# MicrobitBoardExtend.net
KiCad netlist of a schematic drawn in Altium Designer
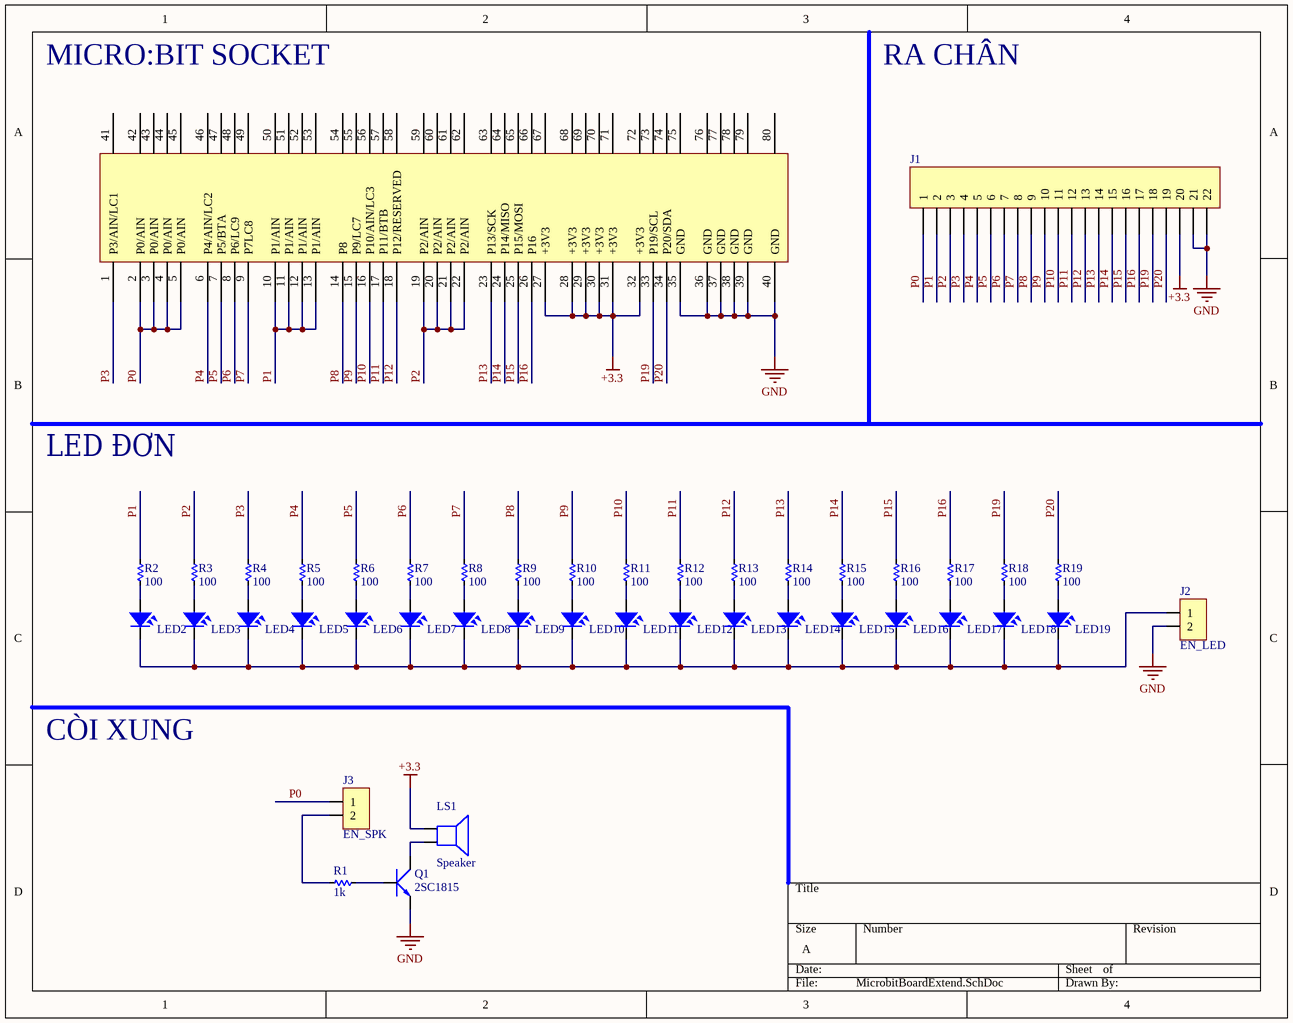
[diagram p0: MicrobitBoardExtend.SchDoc]

(export (version "E")
  (design (tool "Eeschema 10.0.6"))
  (components
    (comp (ref "BBC1")
      (value "BBC_SOCKET")
      (footprint "BBC_SK_DIP")
      (libsource (lib "microbit") (part "BBC_SOCKET"))
    )
    (comp (ref "J1")
      (value "JP22")
      (footprint "JP22-D1T")
      (description "WR-PHD 2.54 mm Angled Socket Header")
      (fields
        (field (name "MANUFACTURER") "Würth Elektronik eiSos GmbH")
        (field (name "PARTNO") "613022143121")
        (field (name "CREATED BY") "Karrer Zheng")
      )
      (libsource (lib "LIBRARY") (part "JP22"))
    )
    (comp (ref "J2")
      (value "EN_LED")
      (footprint "JP2-CLOSED")
      (description "WR-PHD 2.54 mm Angled Socket Header")
      (fields
        (field (name "MANUFACTURER") "Würth Elektronik eiSos GmbH")
        (field (name "PARTNO") "613002143121")
        (field (name "CREATED BY") "Karrer Zheng")
      )
      (libsource (lib "LIBRARY") (part "JP2"))
    )
    (comp (ref "J3")
      (value "EN_SPK")
      (footprint "JP2-CLOSED")
      (description "WR-PHD 2.54 mm Angled Socket Header")
      (fields
        (field (name "MANUFACTURER") "Würth Elektronik eiSos GmbH")
        (field (name "PARTNO") "613002143121")
        (field (name "CREATED BY") "Karrer Zheng")
      )
      (libsource (lib "LIBRARY") (part "JP2"))
    )
    (comp (ref "LED2")
      (value "LED")
      (footprint "LED-3MM-BLUE")
      (description "LED Single colour Green and Red")
      (libsource (lib "LIBRARY") (part "LED"))
    )
    (comp (ref "LED3")
      (value "LED")
      (footprint "LED-3MM-BLUE")
      (description "LED Single colour Green and Red")
      (libsource (lib "LIBRARY") (part "LED"))
    )
    (comp (ref "LED4")
      (value "LED")
      (footprint "LED-3MM-BLUE")
      (description "LED Single colour Green and Red")
      (libsource (lib "LIBRARY") (part "LED"))
    )
    (comp (ref "LED5")
      (value "LED")
      (footprint "LED-3MM-BLUE")
      (description "LED Single colour Green and Red")
      (libsource (lib "LIBRARY") (part "LED"))
    )
    (comp (ref "LED6")
      (value "LED")
      (footprint "LED-3MM-BLUE")
      (description "LED Single colour Green and Red")
      (libsource (lib "LIBRARY") (part "LED"))
    )
    (comp (ref "LED7")
      (value "LED")
      (footprint "LED-3MM-BLUE")
      (description "LED Single colour Green and Red")
      (libsource (lib "LIBRARY") (part "LED"))
    )
    (comp (ref "LED8")
      (value "LED")
      (footprint "LED-3MM-BLUE")
      (description "LED Single colour Green and Red")
      (libsource (lib "LIBRARY") (part "LED"))
    )
    (comp (ref "LED9")
      (value "LED")
      (footprint "LED-3MM-BLUE")
      (description "LED Single colour Green and Red")
      (libsource (lib "LIBRARY") (part "LED"))
    )
    (comp (ref "LED10")
      (value "LED")
      (footprint "LED-3MM-BLUE")
      (description "LED Single colour Green and Red")
      (libsource (lib "LIBRARY") (part "LED"))
    )
    (comp (ref "LED11")
      (value "LED")
      (footprint "LED-3MM-BLUE")
      (description "LED Single colour Green and Red")
      (libsource (lib "LIBRARY") (part "LED"))
    )
    (comp (ref "LED12")
      (value "LED")
      (footprint "LED-3MM-BLUE")
      (description "LED Single colour Green and Red")
      (libsource (lib "LIBRARY") (part "LED"))
    )
    (comp (ref "LED13")
      (value "LED")
      (footprint "LED-3MM-BLUE")
      (description "LED Single colour Green and Red")
      (libsource (lib "LIBRARY") (part "LED"))
    )
    (comp (ref "LED14")
      (value "LED")
      (footprint "LED-3MM-BLUE")
      (description "LED Single colour Green and Red")
      (libsource (lib "LIBRARY") (part "LED"))
    )
    (comp (ref "LED15")
      (value "LED")
      (footprint "LED-3MM-BLUE")
      (description "LED Single colour Green and Red")
      (libsource (lib "LIBRARY") (part "LED"))
    )
    (comp (ref "LED16")
      (value "LED")
      (footprint "LED-3MM-BLUE")
      (description "LED Single colour Green and Red")
      (libsource (lib "LIBRARY") (part "LED"))
    )
    (comp (ref "LED17")
      (value "LED")
      (footprint "LED-3MM-BLUE")
      (description "LED Single colour Green and Red")
      (libsource (lib "LIBRARY") (part "LED"))
    )
    (comp (ref "LED18")
      (value "LED")
      (footprint "LED-3MM-BLUE")
      (description "LED Single colour Green and Red")
      (libsource (lib "LIBRARY") (part "LED"))
    )
    (comp (ref "LED19")
      (value "LED")
      (footprint "LED-3MM-BLUE")
      (description "LED Single colour Green and Red")
      (libsource (lib "LIBRARY") (part "LED"))
    )
    (comp (ref "LS1")
      (value "Speaker")
      (footprint "SPEAKER")
      (description "Loudspeaker")
      (fields (field (name "PUBLISHER") "Altium Limited"))
      (libsource (lib "LIBRARY") (part "Speaker"))
    )
    (comp (ref "Q1")
      (value "2SC1815")
      (footprint "SOT23-321")
      (description "NPN 600mW, ECB")
      (libsource (lib "LIBRARY") (part "2SC1815"))
    )
    (comp (ref "R1")
      (value "1k")
      (footprint "RES-SMD-0805")
      (description "Resistor")
      (fields
        (field (name "MANUFACTURER") "Generic Components")
        (field (name "PUBLISHER") "Altium Hobart Technology Centre")
      )
      (libsource (lib "LIBRARY") (part "Res-SMD"))
    )
    (comp (ref "R2")
      (value "100")
      (footprint "RES-SMD-0805")
      (description "Resistor")
      (fields
        (field (name "MANUFACTURER") "Generic Components")
        (field (name "PUBLISHER") "Altium Hobart Technology Centre")
      )
      (libsource (lib "LIBRARY") (part "Res-SMD"))
    )
    (comp (ref "R3")
      (value "100")
      (footprint "RES-SMD-0805")
      (description "Resistor")
      (fields
        (field (name "MANUFACTURER") "Generic Components")
        (field (name "PUBLISHER") "Altium Hobart Technology Centre")
      )
      (libsource (lib "LIBRARY") (part "Res-SMD"))
    )
    (comp (ref "R4")
      (value "100")
      (footprint "RES-SMD-0805")
      (description "Resistor")
      (fields
        (field (name "MANUFACTURER") "Generic Components")
        (field (name "PUBLISHER") "Altium Hobart Technology Centre")
      )
      (libsource (lib "LIBRARY") (part "Res-SMD"))
    )
    (comp (ref "R5")
      (value "100")
      (footprint "RES-SMD-0805")
      (description "Resistor")
      (fields
        (field (name "MANUFACTURER") "Generic Components")
        (field (name "PUBLISHER") "Altium Hobart Technology Centre")
      )
      (libsource (lib "LIBRARY") (part "Res-SMD"))
    )
    (comp (ref "R6")
      (value "100")
      (footprint "RES-SMD-0805")
      (description "Resistor")
      (fields
        (field (name "MANUFACTURER") "Generic Components")
        (field (name "PUBLISHER") "Altium Hobart Technology Centre")
      )
      (libsource (lib "LIBRARY") (part "Res-SMD"))
    )
    (comp (ref "R7")
      (value "100")
      (footprint "RES-SMD-0805")
      (description "Resistor")
      (fields
        (field (name "MANUFACTURER") "Generic Components")
        (field (name "PUBLISHER") "Altium Hobart Technology Centre")
      )
      (libsource (lib "LIBRARY") (part "Res-SMD"))
    )
    (comp (ref "R8")
      (value "100")
      (footprint "RES-SMD-0805")
      (description "Resistor")
      (fields
        (field (name "MANUFACTURER") "Generic Components")
        (field (name "PUBLISHER") "Altium Hobart Technology Centre")
      )
      (libsource (lib "LIBRARY") (part "Res-SMD"))
    )
    (comp (ref "R9")
      (value "100")
      (footprint "RES-SMD-0805")
      (description "Resistor")
      (fields
        (field (name "MANUFACTURER") "Generic Components")
        (field (name "PUBLISHER") "Altium Hobart Technology Centre")
      )
      (libsource (lib "LIBRARY") (part "Res-SMD"))
    )
    (comp (ref "R10")
      (value "100")
      (footprint "RES-SMD-0805")
      (description "Resistor")
      (fields
        (field (name "MANUFACTURER") "Generic Components")
        (field (name "PUBLISHER") "Altium Hobart Technology Centre")
      )
      (libsource (lib "LIBRARY") (part "Res-SMD"))
    )
    (comp (ref "R11")
      (value "100")
      (footprint "RES-SMD-0805")
      (description "Resistor")
      (fields
        (field (name "MANUFACTURER") "Generic Components")
        (field (name "PUBLISHER") "Altium Hobart Technology Centre")
      )
      (libsource (lib "LIBRARY") (part "Res-SMD"))
    )
    (comp (ref "R12")
      (value "100")
      (footprint "RES-SMD-0805")
      (description "Resistor")
      (fields
        (field (name "MANUFACTURER") "Generic Components")
        (field (name "PUBLISHER") "Altium Hobart Technology Centre")
      )
      (libsource (lib "LIBRARY") (part "Res-SMD"))
    )
    (comp (ref "R13")
      (value "100")
      (footprint "RES-SMD-0805")
      (description "Resistor")
      (fields
        (field (name "MANUFACTURER") "Generic Components")
        (field (name "PUBLISHER") "Altium Hobart Technology Centre")
      )
      (libsource (lib "LIBRARY") (part "Res-SMD"))
    )
    (comp (ref "R14")
      (value "100")
      (footprint "RES-SMD-0805")
      (description "Resistor")
      (fields
        (field (name "MANUFACTURER") "Generic Components")
        (field (name "PUBLISHER") "Altium Hobart Technology Centre")
      )
      (libsource (lib "LIBRARY") (part "Res-SMD"))
    )
    (comp (ref "R15")
      (value "100")
      (footprint "RES-SMD-0805")
      (description "Resistor")
      (fields
        (field (name "MANUFACTURER") "Generic Components")
        (field (name "PUBLISHER") "Altium Hobart Technology Centre")
      )
      (libsource (lib "LIBRARY") (part "Res-SMD"))
    )
    (comp (ref "R16")
      (value "100")
      (footprint "RES-SMD-0805")
      (description "Resistor")
      (fields
        (field (name "MANUFACTURER") "Generic Components")
        (field (name "PUBLISHER") "Altium Hobart Technology Centre")
      )
      (libsource (lib "LIBRARY") (part "Res-SMD"))
    )
    (comp (ref "R17")
      (value "100")
      (footprint "RES-SMD-0805")
      (description "Resistor")
      (fields
        (field (name "MANUFACTURER") "Generic Components")
        (field (name "PUBLISHER") "Altium Hobart Technology Centre")
      )
      (libsource (lib "LIBRARY") (part "Res-SMD"))
    )
    (comp (ref "R18")
      (value "100")
      (footprint "RES-SMD-0805")
      (description "Resistor")
      (fields
        (field (name "MANUFACTURER") "Generic Components")
        (field (name "PUBLISHER") "Altium Hobart Technology Centre")
      )
      (libsource (lib "LIBRARY") (part "Res-SMD"))
    )
    (comp (ref "R19")
      (value "100")
      (footprint "RES-SMD-0805")
      (description "Resistor")
      (fields
        (field (name "MANUFACTURER") "Generic Components")
        (field (name "PUBLISHER") "Altium Hobart Technology Centre")
      )
      (libsource (lib "LIBRARY") (part "Res-SMD"))
    )
  )
  (nets
    (net (code "1") (name "+3.3") (class "Default")
      (node (ref "BBC1") (pin "27") (pinfunction "+3V3_27") (pintype "passive"))
      (node (ref "BBC1") (pin "28") (pinfunction "+3V3_28") (pintype "passive"))
      (node (ref "BBC1") (pin "29") (pinfunction "+3V3_29") (pintype "passive"))
      (node (ref "BBC1") (pin "30") (pinfunction "+3V3_30") (pintype "passive"))
      (node (ref "BBC1") (pin "31") (pinfunction "+3V3_31") (pintype "passive"))
      (node (ref "BBC1") (pin "32") (pinfunction "+3V3_32") (pintype "passive"))
      (node (ref "J1") (pin "20") (pinfunction "20_20") (pintype "passive"))
      (node (ref "LS1") (pin "1") (pinfunction "1_1") (pintype "passive"))
    )
    (net (code "2") (name "/P0") (class "Default")
      (node (ref "BBC1") (pin "2") (pinfunction "P0/AIN_2") (pintype "passive"))
      (node (ref "BBC1") (pin "3") (pinfunction "P0/AIN_3") (pintype "passive"))
      (node (ref "BBC1") (pin "4") (pinfunction "P0/AIN_4") (pintype "passive"))
      (node (ref "BBC1") (pin "5") (pinfunction "P0/AIN_5") (pintype "passive"))
      (node (ref "J1") (pin "1") (pinfunction "1_1") (pintype "passive"))
      (node (ref "J3") (pin "1") (pinfunction "1_1") (pintype "passive"))
    )
    (net (code "3") (name "/P1") (class "Default")
      (node (ref "BBC1") (pin "10") (pinfunction "P1/AIN_10") (pintype "passive"))
      (node (ref "BBC1") (pin "11") (pinfunction "P1/AIN_11") (pintype "passive"))
      (node (ref "BBC1") (pin "12") (pinfunction "P1/AIN_12") (pintype "passive"))
      (node (ref "BBC1") (pin "13") (pinfunction "P1/AIN_13") (pintype "passive"))
      (node (ref "J1") (pin "2") (pinfunction "2_2") (pintype "passive"))
      (node (ref "R2") (pin "2") (pinfunction "2_2") (pintype "passive"))
    )
    (net (code "4") (name "/P2") (class "Default")
      (node (ref "BBC1") (pin "19") (pinfunction "P2/AIN_19") (pintype "passive"))
      (node (ref "BBC1") (pin "20") (pinfunction "P2/AIN_20") (pintype "passive"))
      (node (ref "BBC1") (pin "21") (pinfunction "P2/AIN_21") (pintype "passive"))
      (node (ref "BBC1") (pin "22") (pinfunction "P2/AIN_22") (pintype "passive"))
      (node (ref "J1") (pin "3") (pinfunction "3_3") (pintype "passive"))
      (node (ref "R3") (pin "2") (pinfunction "2_2") (pintype "passive"))
    )
    (net (code "5") (name "/P3") (class "Default")
      (node (ref "BBC1") (pin "1") (pinfunction "P3/AIN/LC1_1") (pintype "passive"))
      (node (ref "J1") (pin "4") (pinfunction "4_4") (pintype "passive"))
      (node (ref "R4") (pin "2") (pinfunction "2_2") (pintype "passive"))
    )
    (net (code "6") (name "/P4") (class "Default")
      (node (ref "BBC1") (pin "6") (pinfunction "P4/AIN/LC2_6") (pintype "passive"))
      (node (ref "J1") (pin "5") (pinfunction "5_5") (pintype "passive"))
      (node (ref "R5") (pin "2") (pinfunction "2_2") (pintype "passive"))
    )
    (net (code "7") (name "/P5") (class "Default")
      (node (ref "BBC1") (pin "7") (pinfunction "P5/BTA_7") (pintype "passive"))
      (node (ref "J1") (pin "6") (pinfunction "6_6") (pintype "passive"))
      (node (ref "R6") (pin "2") (pinfunction "2_2") (pintype "passive"))
    )
    (net (code "8") (name "/P6") (class "Default")
      (node (ref "BBC1") (pin "8") (pinfunction "P6/LC9_8") (pintype "passive"))
      (node (ref "J1") (pin "7") (pinfunction "7_7") (pintype "passive"))
      (node (ref "R7") (pin "2") (pinfunction "2_2") (pintype "passive"))
    )
    (net (code "9") (name "/P7") (class "Default")
      (node (ref "BBC1") (pin "9") (pinfunction "P7LC8_9") (pintype "passive"))
      (node (ref "J1") (pin "8") (pinfunction "8_8") (pintype "passive"))
      (node (ref "R8") (pin "2") (pinfunction "2_2") (pintype "passive"))
    )
    (net (code "10") (name "/P8") (class "Default")
      (node (ref "BBC1") (pin "14") (pinfunction "P8_14") (pintype "passive"))
      (node (ref "J1") (pin "9") (pinfunction "9_9") (pintype "passive"))
      (node (ref "R9") (pin "2") (pinfunction "2_2") (pintype "passive"))
    )
    (net (code "11") (name "/P9") (class "Default")
      (node (ref "BBC1") (pin "15") (pinfunction "P9/LC7_15") (pintype "passive"))
      (node (ref "J1") (pin "10") (pinfunction "10_10") (pintype "passive"))
      (node (ref "R10") (pin "2") (pinfunction "2_2") (pintype "passive"))
    )
    (net (code "12") (name "/P10") (class "Default")
      (node (ref "BBC1") (pin "16") (pinfunction "P10/AIN/LC3_16") (pintype "passive"))
      (node (ref "J1") (pin "11") (pinfunction "11_11") (pintype "passive"))
      (node (ref "R11") (pin "2") (pinfunction "2_2") (pintype "passive"))
    )
    (net (code "13") (name "/P11") (class "Default")
      (node (ref "BBC1") (pin "17") (pinfunction "P11/BTB_17") (pintype "passive"))
      (node (ref "J1") (pin "12") (pinfunction "12_12") (pintype "passive"))
      (node (ref "R12") (pin "2") (pinfunction "2_2") (pintype "passive"))
    )
    (net (code "14") (name "/P12") (class "Default")
      (node (ref "BBC1") (pin "18") (pinfunction "P12/RESERVED_18") (pintype "passive"))
      (node (ref "J1") (pin "13") (pinfunction "13_13") (pintype "passive"))
      (node (ref "R13") (pin "2") (pinfunction "2_2") (pintype "passive"))
    )
    (net (code "15") (name "/P13") (class "Default")
      (node (ref "BBC1") (pin "23") (pinfunction "P13/SCK_23") (pintype "passive"))
      (node (ref "J1") (pin "14") (pinfunction "14_14") (pintype "passive"))
      (node (ref "R14") (pin "2") (pinfunction "2_2") (pintype "passive"))
    )
    (net (code "16") (name "/P14") (class "Default")
      (node (ref "BBC1") (pin "24") (pinfunction "P14/MISO_24") (pintype "passive"))
      (node (ref "J1") (pin "15") (pinfunction "15_15") (pintype "passive"))
      (node (ref "R15") (pin "2") (pinfunction "2_2") (pintype "passive"))
    )
    (net (code "17") (name "/P15") (class "Default")
      (node (ref "BBC1") (pin "25") (pinfunction "P15/MOSI_25") (pintype "passive"))
      (node (ref "J1") (pin "16") (pinfunction "16_16") (pintype "passive"))
      (node (ref "R16") (pin "2") (pinfunction "2_2") (pintype "passive"))
    )
    (net (code "18") (name "/P16") (class "Default")
      (node (ref "BBC1") (pin "26") (pinfunction "P16_26") (pintype "passive"))
      (node (ref "J1") (pin "17") (pinfunction "17_17") (pintype "passive"))
      (node (ref "R17") (pin "2") (pinfunction "2_2") (pintype "passive"))
    )
    (net (code "19") (name "/P19") (class "Default")
      (node (ref "BBC1") (pin "33") (pinfunction "P19/SCL_33") (pintype "passive"))
      (node (ref "J1") (pin "18") (pinfunction "18_18") (pintype "passive"))
      (node (ref "R18") (pin "2") (pinfunction "2_2") (pintype "passive"))
    )
    (net (code "20") (name "/P20") (class "Default")
      (node (ref "BBC1") (pin "34") (pinfunction "P20/SDA_34") (pintype "passive"))
      (node (ref "J1") (pin "19") (pinfunction "19_19") (pintype "passive"))
      (node (ref "R19") (pin "2") (pinfunction "2_2") (pintype "passive"))
    )
    (net (code "21") (name "GND") (class "Default")
      (node (ref "BBC1") (pin "35") (pinfunction "GND_35") (pintype "passive"))
      (node (ref "BBC1") (pin "36") (pinfunction "GND_36") (pintype "passive"))
      (node (ref "BBC1") (pin "37") (pinfunction "GND_37") (pintype "passive"))
      (node (ref "BBC1") (pin "38") (pinfunction "GND_38") (pintype "passive"))
      (node (ref "BBC1") (pin "39") (pinfunction "GND_39") (pintype "passive"))
      (node (ref "BBC1") (pin "40") (pinfunction "GND_40") (pintype "passive"))
      (node (ref "J1") (pin "21") (pinfunction "21_21") (pintype "passive"))
      (node (ref "J1") (pin "22") (pinfunction "22_22") (pintype "passive"))
      (node (ref "J2") (pin "2") (pinfunction "2_2") (pintype "passive"))
      (node (ref "Q1") (pin "1") (pinfunction "E_1") (pintype "passive"))
    )
    (net (code "22") (name "Net-(J2-Pad1)") (class "Default")
      (node (ref "J2") (pin "1") (pinfunction "1_1") (pintype "passive"))
      (node (ref "LED10") (pin "2") (pinfunction "2_2") (pintype "passive"))
      (node (ref "LED11") (pin "2") (pinfunction "2_2") (pintype "passive"))
      (node (ref "LED12") (pin "2") (pinfunction "2_2") (pintype "passive"))
      (node (ref "LED13") (pin "2") (pinfunction "2_2") (pintype "passive"))
      (node (ref "LED14") (pin "2") (pinfunction "2_2") (pintype "passive"))
      (node (ref "LED15") (pin "2") (pinfunction "2_2") (pintype "passive"))
      (node (ref "LED16") (pin "2") (pinfunction "2_2") (pintype "passive"))
      (node (ref "LED17") (pin "2") (pinfunction "2_2") (pintype "passive"))
      (node (ref "LED18") (pin "2") (pinfunction "2_2") (pintype "passive"))
      (node (ref "LED19") (pin "2") (pinfunction "2_2") (pintype "passive"))
      (node (ref "LED2") (pin "2") (pinfunction "2_2") (pintype "passive"))
      (node (ref "LED3") (pin "2") (pinfunction "2_2") (pintype "passive"))
      (node (ref "LED4") (pin "2") (pinfunction "2_2") (pintype "passive"))
      (node (ref "LED5") (pin "2") (pinfunction "2_2") (pintype "passive"))
      (node (ref "LED6") (pin "2") (pinfunction "2_2") (pintype "passive"))
      (node (ref "LED7") (pin "2") (pinfunction "2_2") (pintype "passive"))
      (node (ref "LED8") (pin "2") (pinfunction "2_2") (pintype "passive"))
      (node (ref "LED9") (pin "2") (pinfunction "2_2") (pintype "passive"))
    )
    (net (code "23") (name "Net-(J3-Pad2)") (class "Default")
      (node (ref "J3") (pin "2") (pinfunction "2_2") (pintype "passive"))
      (node (ref "R1") (pin "2") (pinfunction "2_2") (pintype "passive"))
    )
    (net (code "24") (name "Net-(LED2-Pad1)") (class "Default")
      (node (ref "LED2") (pin "1") (pinfunction "1_1") (pintype "passive"))
      (node (ref "R2") (pin "1") (pinfunction "1_1") (pintype "passive"))
    )
    (net (code "25") (name "Net-(LED3-Pad1)") (class "Default")
      (node (ref "LED3") (pin "1") (pinfunction "1_1") (pintype "passive"))
      (node (ref "R3") (pin "1") (pinfunction "1_1") (pintype "passive"))
    )
    (net (code "26") (name "Net-(LED4-Pad1)") (class "Default")
      (node (ref "LED4") (pin "1") (pinfunction "1_1") (pintype "passive"))
      (node (ref "R4") (pin "1") (pinfunction "1_1") (pintype "passive"))
    )
    (net (code "27") (name "Net-(LED5-Pad1)") (class "Default")
      (node (ref "LED5") (pin "1") (pinfunction "1_1") (pintype "passive"))
      (node (ref "R5") (pin "1") (pinfunction "1_1") (pintype "passive"))
    )
    (net (code "28") (name "Net-(LED6-Pad1)") (class "Default")
      (node (ref "LED6") (pin "1") (pinfunction "1_1") (pintype "passive"))
      (node (ref "R6") (pin "1") (pinfunction "1_1") (pintype "passive"))
    )
    (net (code "29") (name "Net-(LED7-Pad1)") (class "Default")
      (node (ref "LED7") (pin "1") (pinfunction "1_1") (pintype "passive"))
      (node (ref "R7") (pin "1") (pinfunction "1_1") (pintype "passive"))
    )
    (net (code "30") (name "Net-(LED8-Pad1)") (class "Default")
      (node (ref "LED8") (pin "1") (pinfunction "1_1") (pintype "passive"))
      (node (ref "R8") (pin "1") (pinfunction "1_1") (pintype "passive"))
    )
    (net (code "31") (name "Net-(LED9-Pad1)") (class "Default")
      (node (ref "LED9") (pin "1") (pinfunction "1_1") (pintype "passive"))
      (node (ref "R9") (pin "1") (pinfunction "1_1") (pintype "passive"))
    )
    (net (code "32") (name "Net-(LED10-Pad1)") (class "Default")
      (node (ref "LED10") (pin "1") (pinfunction "1_1") (pintype "passive"))
      (node (ref "R10") (pin "1") (pinfunction "1_1") (pintype "passive"))
    )
    (net (code "33") (name "Net-(LED11-Pad1)") (class "Default")
      (node (ref "LED11") (pin "1") (pinfunction "1_1") (pintype "passive"))
      (node (ref "R11") (pin "1") (pinfunction "1_1") (pintype "passive"))
    )
    (net (code "34") (name "Net-(LED12-Pad1)") (class "Default")
      (node (ref "LED12") (pin "1") (pinfunction "1_1") (pintype "passive"))
      (node (ref "R12") (pin "1") (pinfunction "1_1") (pintype "passive"))
    )
    (net (code "35") (name "Net-(LED13-Pad1)") (class "Default")
      (node (ref "LED13") (pin "1") (pinfunction "1_1") (pintype "passive"))
      (node (ref "R13") (pin "1") (pinfunction "1_1") (pintype "passive"))
    )
    (net (code "36") (name "Net-(LED14-Pad1)") (class "Default")
      (node (ref "LED14") (pin "1") (pinfunction "1_1") (pintype "passive"))
      (node (ref "R14") (pin "1") (pinfunction "1_1") (pintype "passive"))
    )
    (net (code "37") (name "Net-(LED15-Pad1)") (class "Default")
      (node (ref "LED15") (pin "1") (pinfunction "1_1") (pintype "passive"))
      (node (ref "R15") (pin "1") (pinfunction "1_1") (pintype "passive"))
    )
    (net (code "38") (name "Net-(LED16-Pad1)") (class "Default")
      (node (ref "LED16") (pin "1") (pinfunction "1_1") (pintype "passive"))
      (node (ref "R16") (pin "1") (pinfunction "1_1") (pintype "passive"))
    )
    (net (code "39") (name "Net-(LED17-Pad1)") (class "Default")
      (node (ref "LED17") (pin "1") (pinfunction "1_1") (pintype "passive"))
      (node (ref "R17") (pin "1") (pinfunction "1_1") (pintype "passive"))
    )
    (net (code "40") (name "Net-(LED18-Pad1)") (class "Default")
      (node (ref "LED18") (pin "1") (pinfunction "1_1") (pintype "passive"))
      (node (ref "R18") (pin "1") (pinfunction "1_1") (pintype "passive"))
    )
    (net (code "41") (name "Net-(LED19-Pad1)") (class "Default")
      (node (ref "LED19") (pin "1") (pinfunction "1_1") (pintype "passive"))
      (node (ref "R19") (pin "1") (pinfunction "1_1") (pintype "passive"))
    )
    (net (code "42") (name "Net-(Q1-B)") (class "Default")
      (node (ref "Q1") (pin "3") (pinfunction "B_3") (pintype "passive"))
      (node (ref "R1") (pin "1") (pinfunction "1_1") (pintype "passive"))
    )
    (net (code "43") (name "Net-(Q1-C)") (class "Default")
      (node (ref "LS1") (pin "2") (pinfunction "2_2") (pintype "passive"))
      (node (ref "Q1") (pin "2") (pinfunction "C_2") (pintype "passive"))
    )
    (net (code "44") (name "unconnected-(BBC1-+3V3-Pad67)") (class "Default")
      (node (ref "BBC1") (pin "67") (pinfunction "+3V3_67") (pintype "passive"))
    )
    (net (code "45") (name "unconnected-(BBC1-+3V3-Pad68)") (class "Default")
      (node (ref "BBC1") (pin "68") (pinfunction "+3V3_68") (pintype "passive"))
    )
    (net (code "46") (name "unconnected-(BBC1-+3V3-Pad69)") (class "Default")
      (node (ref "BBC1") (pin "69") (pinfunction "+3V3_69") (pintype "passive"))
    )
    (net (code "47") (name "unconnected-(BBC1-+3V3-Pad70)") (class "Default")
      (node (ref "BBC1") (pin "70") (pinfunction "+3V3_70") (pintype "passive"))
    )
    (net (code "48") (name "unconnected-(BBC1-+3V3-Pad71)") (class "Default")
      (node (ref "BBC1") (pin "71") (pinfunction "+3V3_71") (pintype "passive"))
    )
    (net (code "49") (name "unconnected-(BBC1-+3V3-Pad72)") (class "Default")
      (node (ref "BBC1") (pin "72") (pinfunction "+3V3_72") (pintype "passive"))
    )
    (net (code "50") (name "unconnected-(BBC1-GND-Pad75)") (class "Default")
      (node (ref "BBC1") (pin "75") (pinfunction "GND_75") (pintype "passive"))
    )
    (net (code "51") (name "unconnected-(BBC1-GND-Pad76)") (class "Default")
      (node (ref "BBC1") (pin "76") (pinfunction "GND_76") (pintype "passive"))
    )
    (net (code "52") (name "unconnected-(BBC1-GND-Pad77)") (class "Default")
      (node (ref "BBC1") (pin "77") (pinfunction "GND_77") (pintype "passive"))
    )
    (net (code "53") (name "unconnected-(BBC1-GND-Pad78)") (class "Default")
      (node (ref "BBC1") (pin "78") (pinfunction "GND_78") (pintype "passive"))
    )
    (net (code "54") (name "unconnected-(BBC1-GND-Pad79)") (class "Default")
      (node (ref "BBC1") (pin "79") (pinfunction "GND_79") (pintype "passive"))
    )
    (net (code "55") (name "unconnected-(BBC1-GND-Pad80)") (class "Default")
      (node (ref "BBC1") (pin "80") (pinfunction "GND_80") (pintype "passive"))
    )
    (net (code "56") (name "unconnected-(BBC1-P0-Pad42)") (class "Default")
      (node (ref "BBC1") (pin "42") (pinfunction "P0_42") (pintype "passive"))
    )
    (net (code "57") (name "unconnected-(BBC1-P0-Pad43)") (class "Default")
      (node (ref "BBC1") (pin "43") (pinfunction "P0_43") (pintype "passive"))
    )
    (net (code "58") (name "unconnected-(BBC1-P0-Pad44)") (class "Default")
      (node (ref "BBC1") (pin "44") (pinfunction "P0_44") (pintype "passive"))
    )
    (net (code "59") (name "unconnected-(BBC1-P0-Pad45)") (class "Default")
      (node (ref "BBC1") (pin "45") (pinfunction "P0_45") (pintype "passive"))
    )
    (net (code "60") (name "unconnected-(BBC1-P1-Pad50)") (class "Default")
      (node (ref "BBC1") (pin "50") (pinfunction "P1_50") (pintype "passive"))
    )
    (net (code "61") (name "unconnected-(BBC1-P1-Pad51)") (class "Default")
      (node (ref "BBC1") (pin "51") (pinfunction "P1_51") (pintype "passive"))
    )
    (net (code "62") (name "unconnected-(BBC1-P1-Pad52)") (class "Default")
      (node (ref "BBC1") (pin "52") (pinfunction "P1_52") (pintype "passive"))
    )
    (net (code "63") (name "unconnected-(BBC1-P1-Pad53)") (class "Default")
      (node (ref "BBC1") (pin "53") (pinfunction "P1_53") (pintype "passive"))
    )
    (net (code "64") (name "unconnected-(BBC1-P2-Pad59)") (class "Default")
      (node (ref "BBC1") (pin "59") (pinfunction "P2_59") (pintype "passive"))
    )
    (net (code "65") (name "unconnected-(BBC1-P2-Pad60)") (class "Default")
      (node (ref "BBC1") (pin "60") (pinfunction "P2_60") (pintype "passive"))
    )
    (net (code "66") (name "unconnected-(BBC1-P2-Pad61)") (class "Default")
      (node (ref "BBC1") (pin "61") (pinfunction "P2_61") (pintype "passive"))
    )
    (net (code "67") (name "unconnected-(BBC1-P2-Pad62)") (class "Default")
      (node (ref "BBC1") (pin "62") (pinfunction "P2_62") (pintype "passive"))
    )
    (net (code "68") (name "unconnected-(BBC1-P3-Pad41)") (class "Default")
      (node (ref "BBC1") (pin "41") (pinfunction "P3_41") (pintype "passive"))
    )
    (net (code "69") (name "unconnected-(BBC1-P4-Pad46)") (class "Default")
      (node (ref "BBC1") (pin "46") (pinfunction "P4_46") (pintype "passive"))
    )
    (net (code "70") (name "unconnected-(BBC1-P5-Pad47)") (class "Default")
      (node (ref "BBC1") (pin "47") (pinfunction "P5_47") (pintype "passive"))
    )
    (net (code "71") (name "unconnected-(BBC1-P6-Pad48)") (class "Default")
      (node (ref "BBC1") (pin "48") (pinfunction "P6_48") (pintype "passive"))
    )
    (net (code "72") (name "unconnected-(BBC1-P7-Pad49)") (class "Default")
      (node (ref "BBC1") (pin "49") (pinfunction "P7_49") (pintype "passive"))
    )
    (net (code "73") (name "unconnected-(BBC1-P8-Pad54)") (class "Default")
      (node (ref "BBC1") (pin "54") (pinfunction "P8_54") (pintype "passive"))
    )
    (net (code "74") (name "unconnected-(BBC1-P9-Pad55)") (class "Default")
      (node (ref "BBC1") (pin "55") (pinfunction "P9_55") (pintype "passive"))
    )
    (net (code "75") (name "unconnected-(BBC1-P10-Pad56)") (class "Default")
      (node (ref "BBC1") (pin "56") (pinfunction "P10_56") (pintype "passive"))
    )
    (net (code "76") (name "unconnected-(BBC1-P11-Pad57)") (class "Default")
      (node (ref "BBC1") (pin "57") (pinfunction "P11_57") (pintype "passive"))
    )
    (net (code "77") (name "unconnected-(BBC1-P12-Pad58)") (class "Default")
      (node (ref "BBC1") (pin "58") (pinfunction "P12_58") (pintype "passive"))
    )
    (net (code "78") (name "unconnected-(BBC1-P13-Pad63)") (class "Default")
      (node (ref "BBC1") (pin "63") (pinfunction "P13_63") (pintype "passive"))
    )
    (net (code "79") (name "unconnected-(BBC1-P14-Pad64)") (class "Default")
      (node (ref "BBC1") (pin "64") (pinfunction "P14_64") (pintype "passive"))
    )
    (net (code "80") (name "unconnected-(BBC1-P15-Pad65)") (class "Default")
      (node (ref "BBC1") (pin "65") (pinfunction "P15_65") (pintype "passive"))
    )
    (net (code "81") (name "unconnected-(BBC1-P16-Pad66)") (class "Default")
      (node (ref "BBC1") (pin "66") (pinfunction "P16_66") (pintype "passive"))
    )
    (net (code "82") (name "unconnected-(BBC1-P19-Pad73)") (class "Default")
      (node (ref "BBC1") (pin "73") (pinfunction "P19_73") (pintype "passive"))
    )
    (net (code "83") (name "unconnected-(BBC1-P20-Pad74)") (class "Default")
      (node (ref "BBC1") (pin "74") (pinfunction "P20_74") (pintype "passive"))
    )
  )
)
